# 5portHub.net
KiCad netlist of a schematic drawn in EAGLE
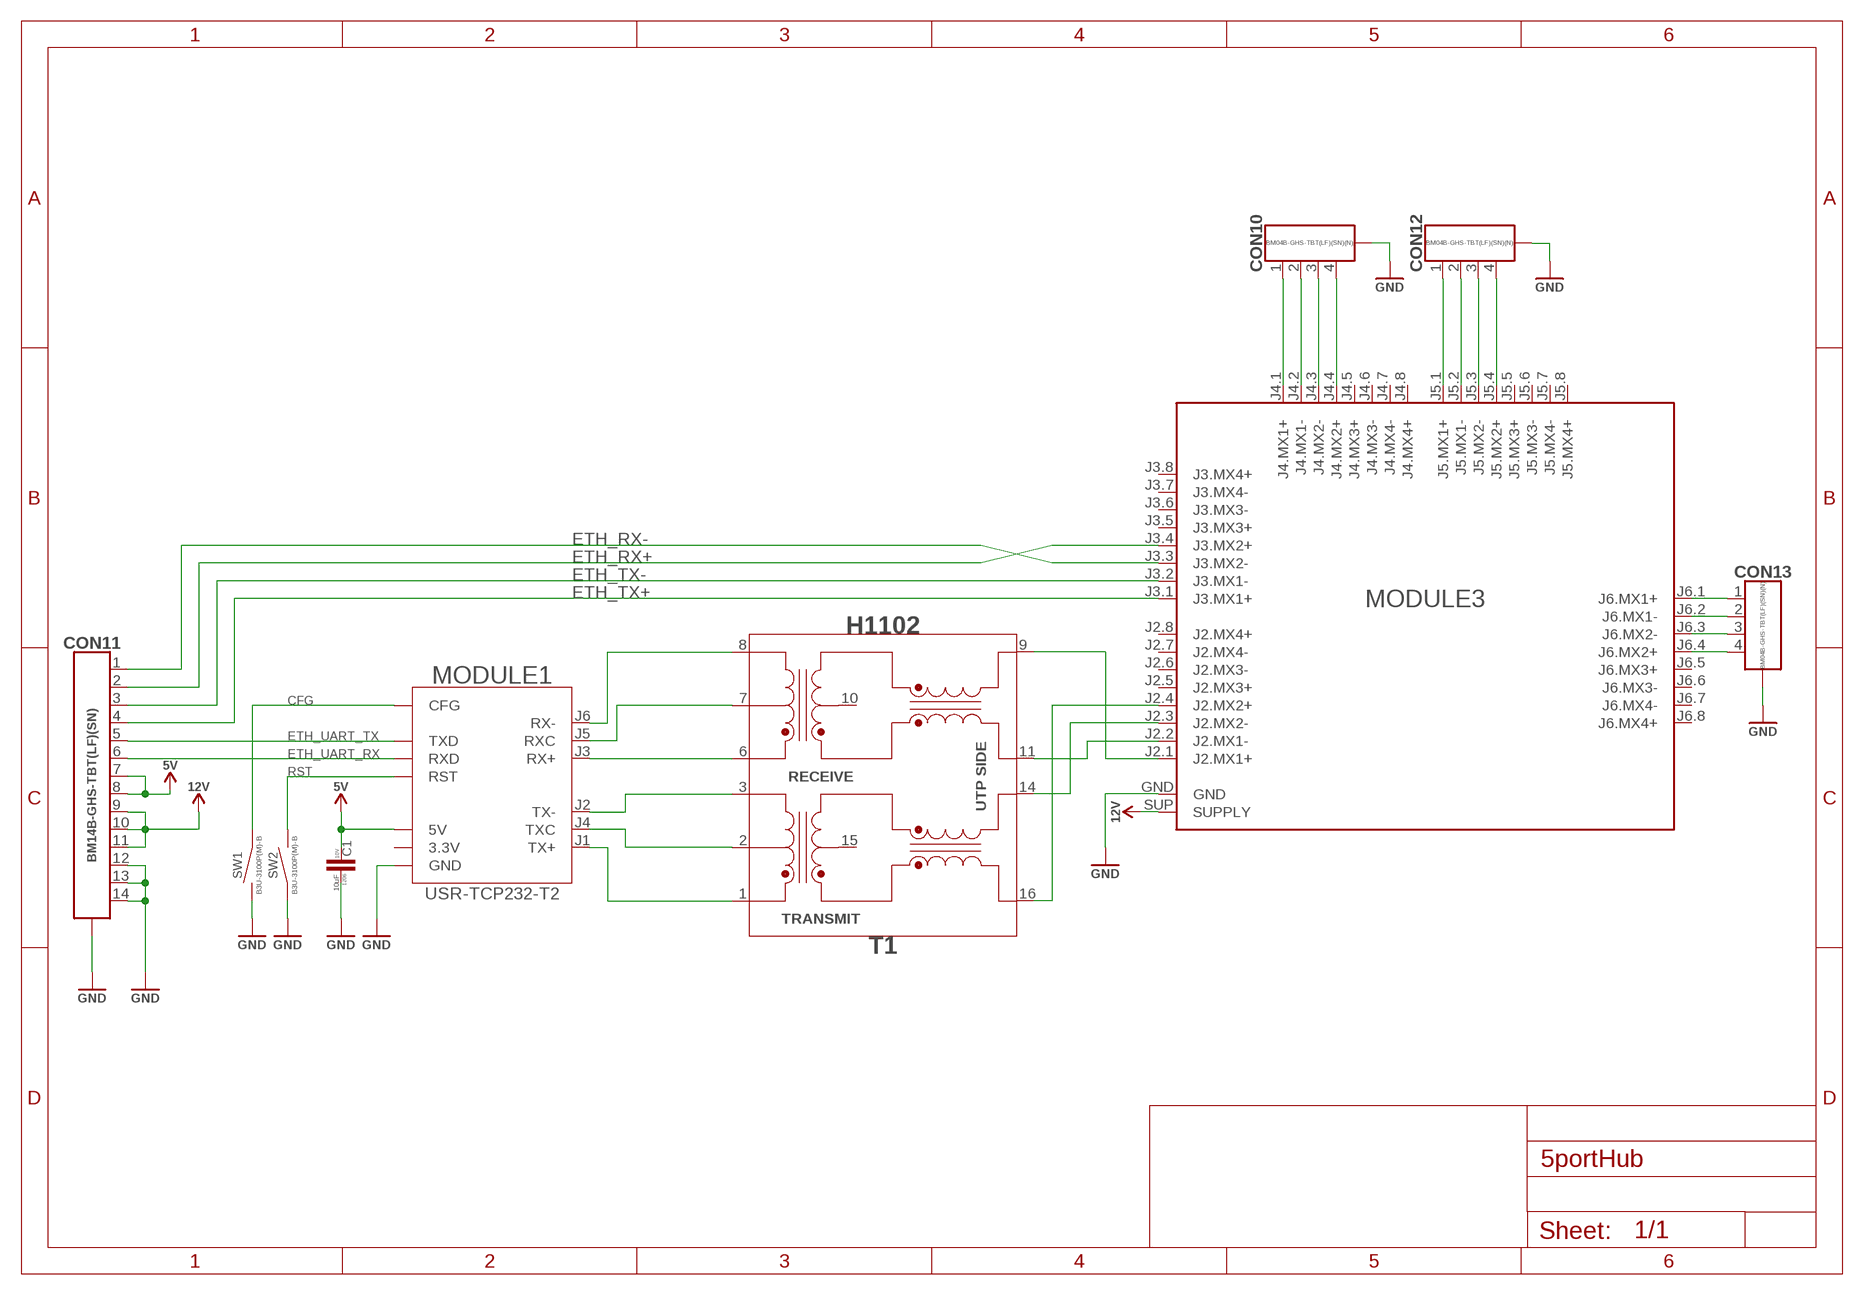
[diagram p0: schematic, sheet 1]

(export (version "E")
  (design (tool "Eeschema 10.0.6"))
  (components
    (comp (ref "C1")
      (value "10uF")
      (footprint "eagle-import:C1206")
      (fields (field (name "PACKAGE") "1206") (field (name "VOLTAGE") "10V"))
      (libsource (lib "eagle-import") (part "C-1206"))
    )
    (comp (ref "CON10")
      (value "CON-4P-TABS-JST-GH-TOP")
      (footprint "eagle-import:BM04B-GHS-TB")
      (fields (field (name "MANF#") "BM04B-GHS-TBT(LF)(SN)(N)") (field (name "MANF") "JST Sales America Inc"))
      (libsource (lib "eagle-import") (part "CON-4P-TABS-JST-GH-TOP"))
    )
    (comp (ref "CON11")
      (value "CON-14P-TABS-JST-GH-TOP")
      (footprint "eagle-import:BM14B-GHS-TBT")
      (fields (field (name "MANF#") "BM14B-GHS-TBT(LF)(SN)") (field (name "MANF") "JST Sales America"))
      (libsource (lib "eagle-import") (part "CON-14P-TABS-JST-GH-TOP"))
    )
    (comp (ref "CON12")
      (value "CON-4P-TABS-JST-GH-TOP")
      (footprint "eagle-import:BM04B-GHS-TB")
      (fields (field (name "MANF#") "BM04B-GHS-TBT(LF)(SN)(N)") (field (name "MANF") "JST Sales America Inc"))
      (libsource (lib "eagle-import") (part "CON-4P-TABS-JST-GH-TOP"))
    )
    (comp (ref "CON13")
      (value "CON-4P-TABS-JST-GH-TOP")
      (footprint "eagle-import:BM04B-GHS-TB")
      (fields (field (name "MANF#") "BM04B-GHS-TBT(LF)(SN)(N)") (field (name "MANF") "JST Sales America Inc"))
      (libsource (lib "eagle-import") (part "CON-4P-TABS-JST-GH-TOP"))
    )
    (comp (ref "MODULE1")
      (value "USR-TCP232-T2")
      (footprint "eagle-import:USR-TCP232-T2")
      (fields (field (name "MANF#") "USR-TCP232-T2") (field (name "MANF") "Waveshare"))
      (libsource (lib "eagle-import") (part "USR-TCP232-T2"))
    )
    (comp (ref "MODULE3")
      (value "ANDDEAR_5PORT3")
      (footprint "eagle-import:ANDDEAR_5PORT3")
      (libsource (lib "eagle-import") (part "ANDDEAR_5PORT3"))
    )
    (comp (ref "SW1")
      (value "TACT_SWITCH-B3U-3100P(M)-B")
      (footprint "eagle-import:B3U-3100P(M)-B")
      (fields (field (name "MANF") "OMRON"))
      (libsource (lib "eagle-import") (part "TACT_SWITCH-B3U-3100P(M)-B"))
    )
    (comp (ref "SW2")
      (value "TACT_SWITCH-B3U-3100P(M)-B")
      (footprint "eagle-import:B3U-3100P(M)-B")
      (fields (field (name "MANF") "OMRON"))
      (libsource (lib "eagle-import") (part "TACT_SWITCH-B3U-3100P(M)-B"))
    )
    (comp (ref "T1")
      (value "H1102NL")
      (footprint "eagle-import:H1102")
      (fields (field (name "MANF") "Pulse Electronics Corporation"))
      (libsource (lib "eagle-import") (part "H1102NL"))
    )
  )
  (nets
    (net (code "1") (name "/CFG") (class "Default")
      (node (ref "MODULE1") (pin "CFG") (pinfunction "CFG_CFG") (pintype "bidirectional"))
      (node (ref "SW1") (pin "P$1") (pinfunction "1_P$1") (pintype "bidirectional"))
    )
    (net (code "2") (name "/ETH_RX+") (class "Default")
      (node (ref "CON11") (pin "2") (pinfunction "2_2") (pintype "passive"))
      (node (ref "MODULE3") (pin "J3.4") (pinfunction "J3.MX2+_J3.4") (pintype "bidirectional"))
    )
    (net (code "3") (name "/ETH_RX-") (class "Default")
      (node (ref "CON11") (pin "1") (pinfunction "1_1") (pintype "passive"))
      (node (ref "MODULE3") (pin "J3.3") (pinfunction "J3.MX2-_J3.3") (pintype "bidirectional"))
    )
    (net (code "4") (name "/ETH_TX+") (class "Default")
      (node (ref "CON11") (pin "4") (pinfunction "4_4") (pintype "passive"))
      (node (ref "MODULE3") (pin "J3.1") (pinfunction "J3.MX1+_J3.1") (pintype "bidirectional"))
    )
    (net (code "5") (name "/ETH_TX-") (class "Default")
      (node (ref "CON11") (pin "3") (pinfunction "3_3") (pintype "passive"))
      (node (ref "MODULE3") (pin "J3.2") (pinfunction "J3.MX1-_J3.2") (pintype "bidirectional"))
    )
    (net (code "6") (name "/ETH_UART_RX") (class "Default")
      (node (ref "CON11") (pin "6") (pinfunction "6_6") (pintype "passive"))
      (node (ref "MODULE1") (pin "RXD") (pinfunction "RXD_RXD") (pintype "bidirectional"))
    )
    (net (code "7") (name "/ETH_UART_TX") (class "Default")
      (node (ref "CON11") (pin "5") (pinfunction "5_5") (pintype "passive"))
      (node (ref "MODULE1") (pin "TXD") (pinfunction "TXD_TXD") (pintype "bidirectional"))
    )
    (net (code "8") (name "/RST") (class "Default")
      (node (ref "MODULE1") (pin "RST") (pinfunction "RST_RST") (pintype "bidirectional"))
      (node (ref "SW2") (pin "P$2") (pinfunction "2_P$2") (pintype "bidirectional"))
    )
    (net (code "9") (name "5V") (class "Default")
      (node (ref "C1") (pin "P$2") (pinfunction "2_P$2") (pintype "passive"))
      (node (ref "CON11") (pin "7") (pinfunction "7_7") (pintype "passive"))
      (node (ref "CON11") (pin "8") (pinfunction "8_8") (pintype "passive"))
      (node (ref "MODULE1") (pin "5V") (pinfunction "5V_5V") (pintype "bidirectional"))
    )
    (net (code "10") (name "12V") (class "Default")
      (node (ref "CON11") (pin "10") (pinfunction "10_10") (pintype "passive"))
      (node (ref "CON11") (pin "11") (pinfunction "11_11") (pintype "passive"))
      (node (ref "CON11") (pin "9") (pinfunction "9_9") (pintype "passive"))
      (node (ref "MODULE3") (pin "SUP") (pinfunction "SUPPLY_SUP") (pintype "bidirectional"))
    )
    (net (code "11") (name "GND") (class "Default")
      (node (ref "C1") (pin "P$1") (pinfunction "1_P$1") (pintype "passive"))
      (node (ref "CON10") (pin "M$0") (pinfunction "GND_M$0") (pintype "bidirectional"))
      (node (ref "CON10") (pin "M$1") (pinfunction "GND_M$1") (pintype "bidirectional"))
      (node (ref "CON11") (pin "12") (pinfunction "12_12") (pintype "passive"))
      (node (ref "CON11") (pin "13") (pinfunction "13_13") (pintype "passive"))
      (node (ref "CON11") (pin "14") (pinfunction "14_14") (pintype "passive"))
      (node (ref "CON11") (pin "M$0") (pinfunction "G1_M$0") (pintype "passive"))
      (node (ref "CON11") (pin "M$1") (pinfunction "G1_M$1") (pintype "passive"))
      (node (ref "CON12") (pin "M$0") (pinfunction "GND_M$0") (pintype "bidirectional"))
      (node (ref "CON12") (pin "M$1") (pinfunction "GND_M$1") (pintype "bidirectional"))
      (node (ref "CON13") (pin "M$0") (pinfunction "GND_M$0") (pintype "bidirectional"))
      (node (ref "CON13") (pin "M$1") (pinfunction "GND_M$1") (pintype "bidirectional"))
      (node (ref "MODULE1") (pin "GND") (pinfunction "GND_GND") (pintype "bidirectional"))
      (node (ref "MODULE3") (pin "GND") (pinfunction "GND_GND") (pintype "bidirectional"))
      (node (ref "SW1") (pin "P$2") (pinfunction "2_P$2") (pintype "bidirectional"))
      (node (ref "SW2") (pin "P$1") (pinfunction "1_P$1") (pintype "bidirectional"))
    )
    (net (code "12") (name "Net-(MODULE1-RX+)") (class "Default")
      (node (ref "MODULE1") (pin "J3") (pinfunction "RX+_J3") (pintype "bidirectional"))
      (node (ref "T1") (pin "6") (pinfunction "6_6") (pintype "bidirectional"))
    )
    (net (code "13") (name "Net-(MODULE1-RX-)") (class "Default")
      (node (ref "MODULE1") (pin "J6") (pinfunction "RX-_J6") (pintype "bidirectional"))
      (node (ref "T1") (pin "8") (pinfunction "8_8") (pintype "bidirectional"))
    )
    (net (code "14") (name "Net-(MODULE1-RXC)") (class "Default")
      (node (ref "MODULE1") (pin "J5") (pinfunction "RXC_J5") (pintype "bidirectional"))
      (node (ref "T1") (pin "7") (pinfunction "7_7") (pintype "bidirectional"))
    )
    (net (code "15") (name "Net-(MODULE1-TX+)") (class "Default")
      (node (ref "MODULE1") (pin "J1") (pinfunction "TX+_J1") (pintype "bidirectional"))
      (node (ref "T1") (pin "1") (pinfunction "1_1") (pintype "bidirectional"))
    )
    (net (code "16") (name "Net-(MODULE1-TX-)") (class "Default")
      (node (ref "MODULE1") (pin "J2") (pinfunction "TX-_J2") (pintype "bidirectional"))
      (node (ref "T1") (pin "3") (pinfunction "3_3") (pintype "bidirectional"))
    )
    (net (code "17") (name "Net-(MODULE1-TXC)") (class "Default")
      (node (ref "MODULE1") (pin "J4") (pinfunction "TXC_J4") (pintype "bidirectional"))
      (node (ref "T1") (pin "2") (pinfunction "2_2") (pintype "bidirectional"))
    )
    (net (code "18") (name "Net-(MODULE3-J2.MX1+)") (class "Default")
      (node (ref "MODULE3") (pin "J2.1") (pinfunction "J2.MX1+_J2.1") (pintype "bidirectional"))
      (node (ref "T1") (pin "9") (pinfunction "9_9") (pintype "bidirectional"))
    )
    (net (code "19") (name "Net-(MODULE3-J2.MX1-)") (class "Default")
      (node (ref "MODULE3") (pin "J2.2") (pinfunction "J2.MX1-_J2.2") (pintype "bidirectional"))
      (node (ref "T1") (pin "11") (pinfunction "11_11") (pintype "bidirectional"))
    )
    (net (code "20") (name "Net-(MODULE3-J2.MX2+)") (class "Default")
      (node (ref "MODULE3") (pin "J2.4") (pinfunction "J2.MX2+_J2.4") (pintype "bidirectional"))
      (node (ref "T1") (pin "16") (pinfunction "16_16") (pintype "bidirectional"))
    )
    (net (code "21") (name "Net-(MODULE3-J2.MX2-)") (class "Default")
      (node (ref "MODULE3") (pin "J2.3") (pinfunction "J2.MX2-_J2.3") (pintype "bidirectional"))
      (node (ref "T1") (pin "14") (pinfunction "14_14") (pintype "bidirectional"))
    )
    (net (code "22") (name "Net-(MODULE3-J4.MX1+)") (class "Default")
      (node (ref "CON10") (pin "1") (pinfunction "1_1") (pintype "bidirectional"))
      (node (ref "MODULE3") (pin "J4.1") (pinfunction "J4.MX1+_J4.1") (pintype "bidirectional"))
    )
    (net (code "23") (name "Net-(MODULE3-J4.MX1-)") (class "Default")
      (node (ref "CON10") (pin "2") (pinfunction "2_2") (pintype "bidirectional"))
      (node (ref "MODULE3") (pin "J4.2") (pinfunction "J4.MX1-_J4.2") (pintype "bidirectional"))
    )
    (net (code "24") (name "Net-(MODULE3-J4.MX2+)") (class "Default")
      (node (ref "CON10") (pin "4") (pinfunction "4_4") (pintype "bidirectional"))
      (node (ref "MODULE3") (pin "J4.4") (pinfunction "J4.MX2+_J4.4") (pintype "bidirectional"))
    )
    (net (code "25") (name "Net-(MODULE3-J4.MX2-)") (class "Default")
      (node (ref "CON10") (pin "3") (pinfunction "3_3") (pintype "bidirectional"))
      (node (ref "MODULE3") (pin "J4.3") (pinfunction "J4.MX2-_J4.3") (pintype "bidirectional"))
    )
    (net (code "26") (name "Net-(MODULE3-J5.MX1+)") (class "Default")
      (node (ref "CON12") (pin "1") (pinfunction "1_1") (pintype "bidirectional"))
      (node (ref "MODULE3") (pin "J5.1") (pinfunction "J5.MX1+_J5.1") (pintype "bidirectional"))
    )
    (net (code "27") (name "Net-(MODULE3-J5.MX1-)") (class "Default")
      (node (ref "CON12") (pin "2") (pinfunction "2_2") (pintype "bidirectional"))
      (node (ref "MODULE3") (pin "J5.2") (pinfunction "J5.MX1-_J5.2") (pintype "bidirectional"))
    )
    (net (code "28") (name "Net-(MODULE3-J5.MX2+)") (class "Default")
      (node (ref "CON12") (pin "4") (pinfunction "4_4") (pintype "bidirectional"))
      (node (ref "MODULE3") (pin "J5.4") (pinfunction "J5.MX2+_J5.4") (pintype "bidirectional"))
    )
    (net (code "29") (name "Net-(MODULE3-J5.MX2-)") (class "Default")
      (node (ref "CON12") (pin "3") (pinfunction "3_3") (pintype "bidirectional"))
      (node (ref "MODULE3") (pin "J5.3") (pinfunction "J5.MX2-_J5.3") (pintype "bidirectional"))
    )
    (net (code "30") (name "Net-(MODULE3-J6.MX1+)") (class "Default")
      (node (ref "CON13") (pin "1") (pinfunction "1_1") (pintype "bidirectional"))
      (node (ref "MODULE3") (pin "J6.1") (pinfunction "J6.MX1+_J6.1") (pintype "bidirectional"))
    )
    (net (code "31") (name "Net-(MODULE3-J6.MX1-)") (class "Default")
      (node (ref "CON13") (pin "2") (pinfunction "2_2") (pintype "bidirectional"))
      (node (ref "MODULE3") (pin "J6.2") (pinfunction "J6.MX1-_J6.2") (pintype "bidirectional"))
    )
    (net (code "32") (name "Net-(MODULE3-J6.MX2+)") (class "Default")
      (node (ref "CON13") (pin "4") (pinfunction "4_4") (pintype "bidirectional"))
      (node (ref "MODULE3") (pin "J6.4") (pinfunction "J6.MX2+_J6.4") (pintype "bidirectional"))
    )
    (net (code "33") (name "Net-(MODULE3-J6.MX2-)") (class "Default")
      (node (ref "CON13") (pin "3") (pinfunction "3_3") (pintype "bidirectional"))
      (node (ref "MODULE3") (pin "J6.3") (pinfunction "J6.MX2-_J6.3") (pintype "bidirectional"))
    )
    (net (code "34") (name "unconnected-(MODULE1-Pad3.3V)") (class "Default")
      (node (ref "MODULE1") (pin "3.3V") (pinfunction "3.3V_3.3V") (pintype "bidirectional"))
    )
    (net (code "35") (name "unconnected-(MODULE3-J2.MX3+-PadJ2.5)") (class "Default")
      (node (ref "MODULE3") (pin "J2.5") (pinfunction "J2.MX3+_J2.5") (pintype "bidirectional"))
    )
    (net (code "36") (name "unconnected-(MODULE3-J2.MX3--PadJ2.6)") (class "Default")
      (node (ref "MODULE3") (pin "J2.6") (pinfunction "J2.MX3-_J2.6") (pintype "bidirectional"))
    )
    (net (code "37") (name "unconnected-(MODULE3-J2.MX4+-PadJ2.8)") (class "Default")
      (node (ref "MODULE3") (pin "J2.8") (pinfunction "J2.MX4+_J2.8") (pintype "bidirectional"))
    )
    (net (code "38") (name "unconnected-(MODULE3-J2.MX4--PadJ2.7)") (class "Default")
      (node (ref "MODULE3") (pin "J2.7") (pinfunction "J2.MX4-_J2.7") (pintype "bidirectional"))
    )
    (net (code "39") (name "unconnected-(MODULE3-J3.MX3+-PadJ3.5)") (class "Default")
      (node (ref "MODULE3") (pin "J3.5") (pinfunction "J3.MX3+_J3.5") (pintype "bidirectional"))
    )
    (net (code "40") (name "unconnected-(MODULE3-J3.MX3--PadJ3.6)") (class "Default")
      (node (ref "MODULE3") (pin "J3.6") (pinfunction "J3.MX3-_J3.6") (pintype "bidirectional"))
    )
    (net (code "41") (name "unconnected-(MODULE3-J3.MX4+-PadJ3.8)") (class "Default")
      (node (ref "MODULE3") (pin "J3.8") (pinfunction "J3.MX4+_J3.8") (pintype "bidirectional"))
    )
    (net (code "42") (name "unconnected-(MODULE3-J3.MX4--PadJ3.7)") (class "Default")
      (node (ref "MODULE3") (pin "J3.7") (pinfunction "J3.MX4-_J3.7") (pintype "bidirectional"))
    )
    (net (code "43") (name "unconnected-(MODULE3-J4.MX3+-PadJ4.5)") (class "Default")
      (node (ref "MODULE3") (pin "J4.5") (pinfunction "J4.MX3+_J4.5") (pintype "bidirectional"))
    )
    (net (code "44") (name "unconnected-(MODULE3-J4.MX3--PadJ4.6)") (class "Default")
      (node (ref "MODULE3") (pin "J4.6") (pinfunction "J4.MX3-_J4.6") (pintype "bidirectional"))
    )
    (net (code "45") (name "unconnected-(MODULE3-J4.MX4+-PadJ4.8)") (class "Default")
      (node (ref "MODULE3") (pin "J4.8") (pinfunction "J4.MX4+_J4.8") (pintype "bidirectional"))
    )
    (net (code "46") (name "unconnected-(MODULE3-J4.MX4--PadJ4.7)") (class "Default")
      (node (ref "MODULE3") (pin "J4.7") (pinfunction "J4.MX4-_J4.7") (pintype "bidirectional"))
    )
    (net (code "47") (name "unconnected-(MODULE3-J5.MX3+-PadJ5.5)") (class "Default")
      (node (ref "MODULE3") (pin "J5.5") (pinfunction "J5.MX3+_J5.5") (pintype "bidirectional"))
    )
    (net (code "48") (name "unconnected-(MODULE3-J5.MX3--PadJ5.6)") (class "Default")
      (node (ref "MODULE3") (pin "J5.6") (pinfunction "J5.MX3-_J5.6") (pintype "bidirectional"))
    )
    (net (code "49") (name "unconnected-(MODULE3-J5.MX4+-PadJ5.8)") (class "Default")
      (node (ref "MODULE3") (pin "J5.8") (pinfunction "J5.MX4+_J5.8") (pintype "bidirectional"))
    )
    (net (code "50") (name "unconnected-(MODULE3-J5.MX4--PadJ5.7)") (class "Default")
      (node (ref "MODULE3") (pin "J5.7") (pinfunction "J5.MX4-_J5.7") (pintype "bidirectional"))
    )
    (net (code "51") (name "unconnected-(MODULE3-J6.MX3+-PadJ6.5)") (class "Default")
      (node (ref "MODULE3") (pin "J6.5") (pinfunction "J6.MX3+_J6.5") (pintype "bidirectional"))
    )
    (net (code "52") (name "unconnected-(MODULE3-J6.MX3--PadJ6.6)") (class "Default")
      (node (ref "MODULE3") (pin "J6.6") (pinfunction "J6.MX3-_J6.6") (pintype "bidirectional"))
    )
    (net (code "53") (name "unconnected-(MODULE3-J6.MX4+-PadJ6.8)") (class "Default")
      (node (ref "MODULE3") (pin "J6.8") (pinfunction "J6.MX4+_J6.8") (pintype "bidirectional"))
    )
    (net (code "54") (name "unconnected-(MODULE3-J6.MX4--PadJ6.7)") (class "Default")
      (node (ref "MODULE3") (pin "J6.7") (pinfunction "J6.MX4-_J6.7") (pintype "bidirectional"))
    )
    (net (code "55") (name "unconnected-(T1-Pad10)") (class "Default")
      (node (ref "T1") (pin "10") (pinfunction "10_10") (pintype "bidirectional"))
    )
    (net (code "56") (name "unconnected-(T1-Pad15)") (class "Default")
      (node (ref "T1") (pin "15") (pinfunction "15_15") (pintype "bidirectional"))
    )
  )
)
